# CAN.net
KiCad netlist of a schematic drawn in Altium Designer
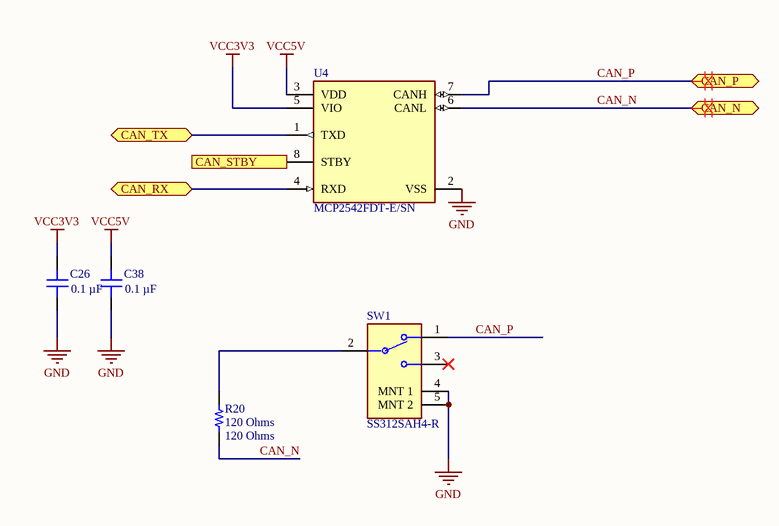
[diagram p0: CAN.SchDoc]

(export (version "E")
  (design (tool "Eeschema 10.0.6"))
  (components
    (comp (ref "C26")
      (value "0.1 µF")
      (footprint "CAP 0805_2012")
      (description "CAP CER 0.1UF 50V X7R 0805")
      (fields (field (name "PART NUMBER") "CC0805MRX7R9BB104") (field (name "MANUFACTURER") "Yageo"))
      (libsource (lib "Celestial Altium Library - altium_library") (part "Capacitor"))
    )
    (comp (ref "C38")
      (value "0.1 µF")
      (footprint "CAP 0805_2012")
      (description "CAP CER 0.1UF 50V X7R 0805")
      (fields (field (name "PART NUMBER") "CC0805MRX7R9BB104") (field (name "MANUFACTURER") "Yageo"))
      (libsource (lib "Celestial Altium Library - altium_library") (part "Capacitor"))
    )
    (comp (ref "R20")
      (value "120 Ohms")
      (footprint "RES 0805_2012")
      (description "RES SMD 120 OHM 1% 1/8W 0805")
      (fields (field (name "PART NUMBER") "ERJ-6ENF1200V") (field (name "ALTIUM_VALUE") "120 Ohms"))
      (libsource (lib "Celestial Altium Library - altium_library") (part "Resistor"))
    )
    (comp (ref "SW1")
      (value "SS312SAH4-R")
      (footprint "FP-SS312SAH4-R-MFG")
      (description "SWITCH SLIDE SPDT 0.4VA 28V")
      (libsource (lib "Altium Content Vault") (part "4c976abc4051e389b5557946779e9a3"))
    )
    (comp (ref "U4")
      (value "MCP2542FDT-E/SN")
      (footprint "FP-C04-057-SN-IPC_C")
      (description "IC TRANSCEIVER 1/1 8SOIC")
      (libsource (lib "Altium Content Vault") (part "c0b3786e5a25f542f02164a957bd85f"))
    )
  )
  (nets
    (net (code "1") (name "/CAN_N") (class "Default")
      (node (ref "R20") (pin "1") (pinfunction "1_1") (pintype "passive"))
      (node (ref "U4") (pin "6") (pinfunction "CANL_6") (pintype "bidirectional"))
    )
    (net (code "2") (name "/CAN_P") (class "Default")
      (node (ref "SW1") (pin "1") (pinfunction "1_1") (pintype "passive"))
      (node (ref "U4") (pin "7") (pinfunction "CANH_7") (pintype "bidirectional"))
    )
    (net (code "3") (name "/CAN_RX") (class "Default")
      (node (ref "U4") (pin "4") (pinfunction "RXD_4") (pintype "input"))
    )
    (net (code "4") (name "/CAN_STBY") (class "Default")
      (node (ref "U4") (pin "8") (pinfunction "STBY_8") (pintype "passive"))
    )
    (net (code "5") (name "/CAN_TX") (class "Default")
      (node (ref "U4") (pin "1") (pinfunction "TXD_1") (pintype "output"))
    )
    (net (code "6") (name "GND") (class "Default")
      (node (ref "C26") (pin "1") (pinfunction "1_1") (pintype "passive"))
      (node (ref "C38") (pin "1") (pinfunction "1_1") (pintype "passive"))
      (node (ref "SW1") (pin "4") (pinfunction "MNT_1_4") (pintype "passive"))
      (node (ref "SW1") (pin "5") (pinfunction "MNT_2_5") (pintype "passive"))
      (node (ref "U4") (pin "2") (pinfunction "VSS_2") (pintype "power_in"))
    )
    (net (code "7") (name "Net-(SW1-COM)") (class "Default")
      (node (ref "R20") (pin "2") (pinfunction "2_2") (pintype "passive"))
      (node (ref "SW1") (pin "2") (pinfunction "COM_2") (pintype "passive"))
    )
    (net (code "8") (name "VCC3V3") (class "Default")
      (node (ref "C26") (pin "2") (pinfunction "2_2") (pintype "passive"))
      (node (ref "U4") (pin "5") (pinfunction "VIO_5") (pintype "power_in"))
    )
    (net (code "9") (name "VCC5V") (class "Default")
      (node (ref "C38") (pin "2") (pinfunction "2_2") (pintype "passive"))
      (node (ref "U4") (pin "3") (pinfunction "VDD_3") (pintype "power_in"))
    )
    (net (code "10") (name "unconnected-(SW1-Pad3)") (class "Default")
      (node (ref "SW1") (pin "3") (pinfunction "3_3") (pintype "passive+no_connect"))
    )
  )
)
